# Frankie_KIT.net
KiCad netlist of a schematic drawn in EAGLE
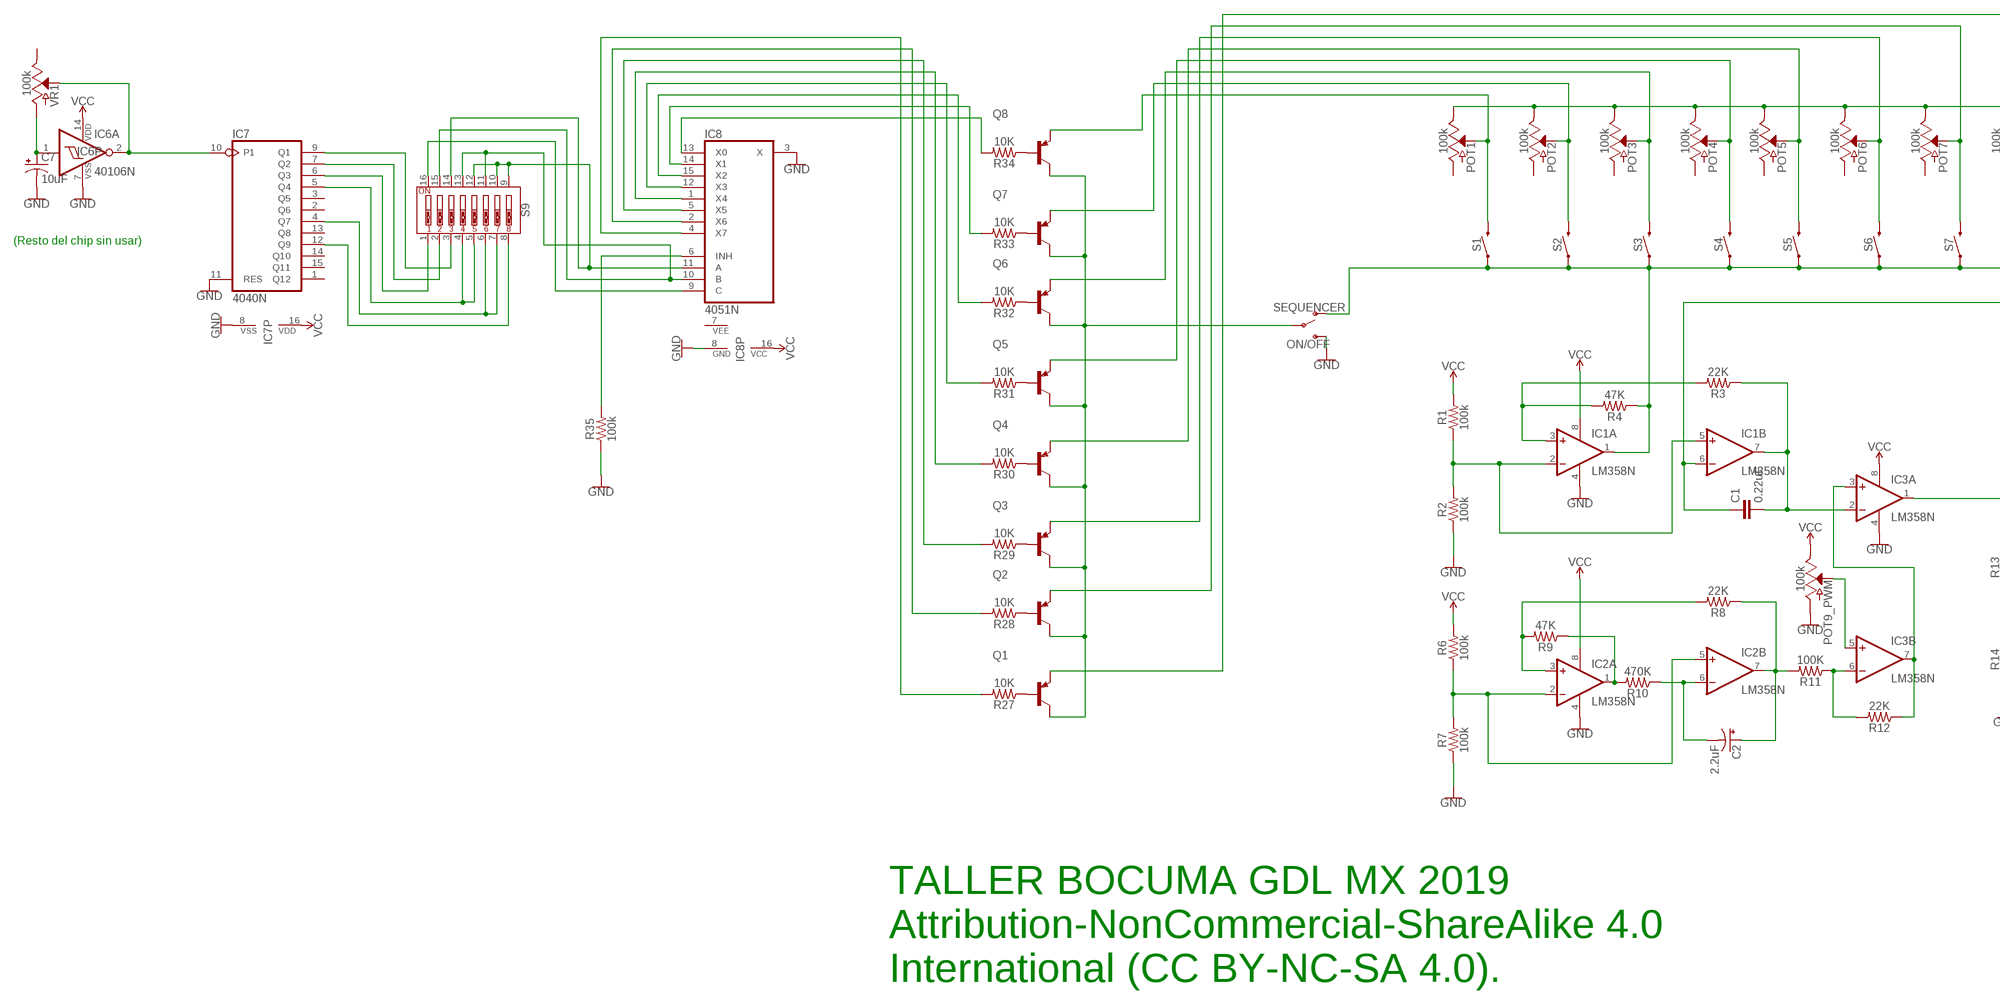
[diagram p0: schematic, sheet 1, part 1 of 2]
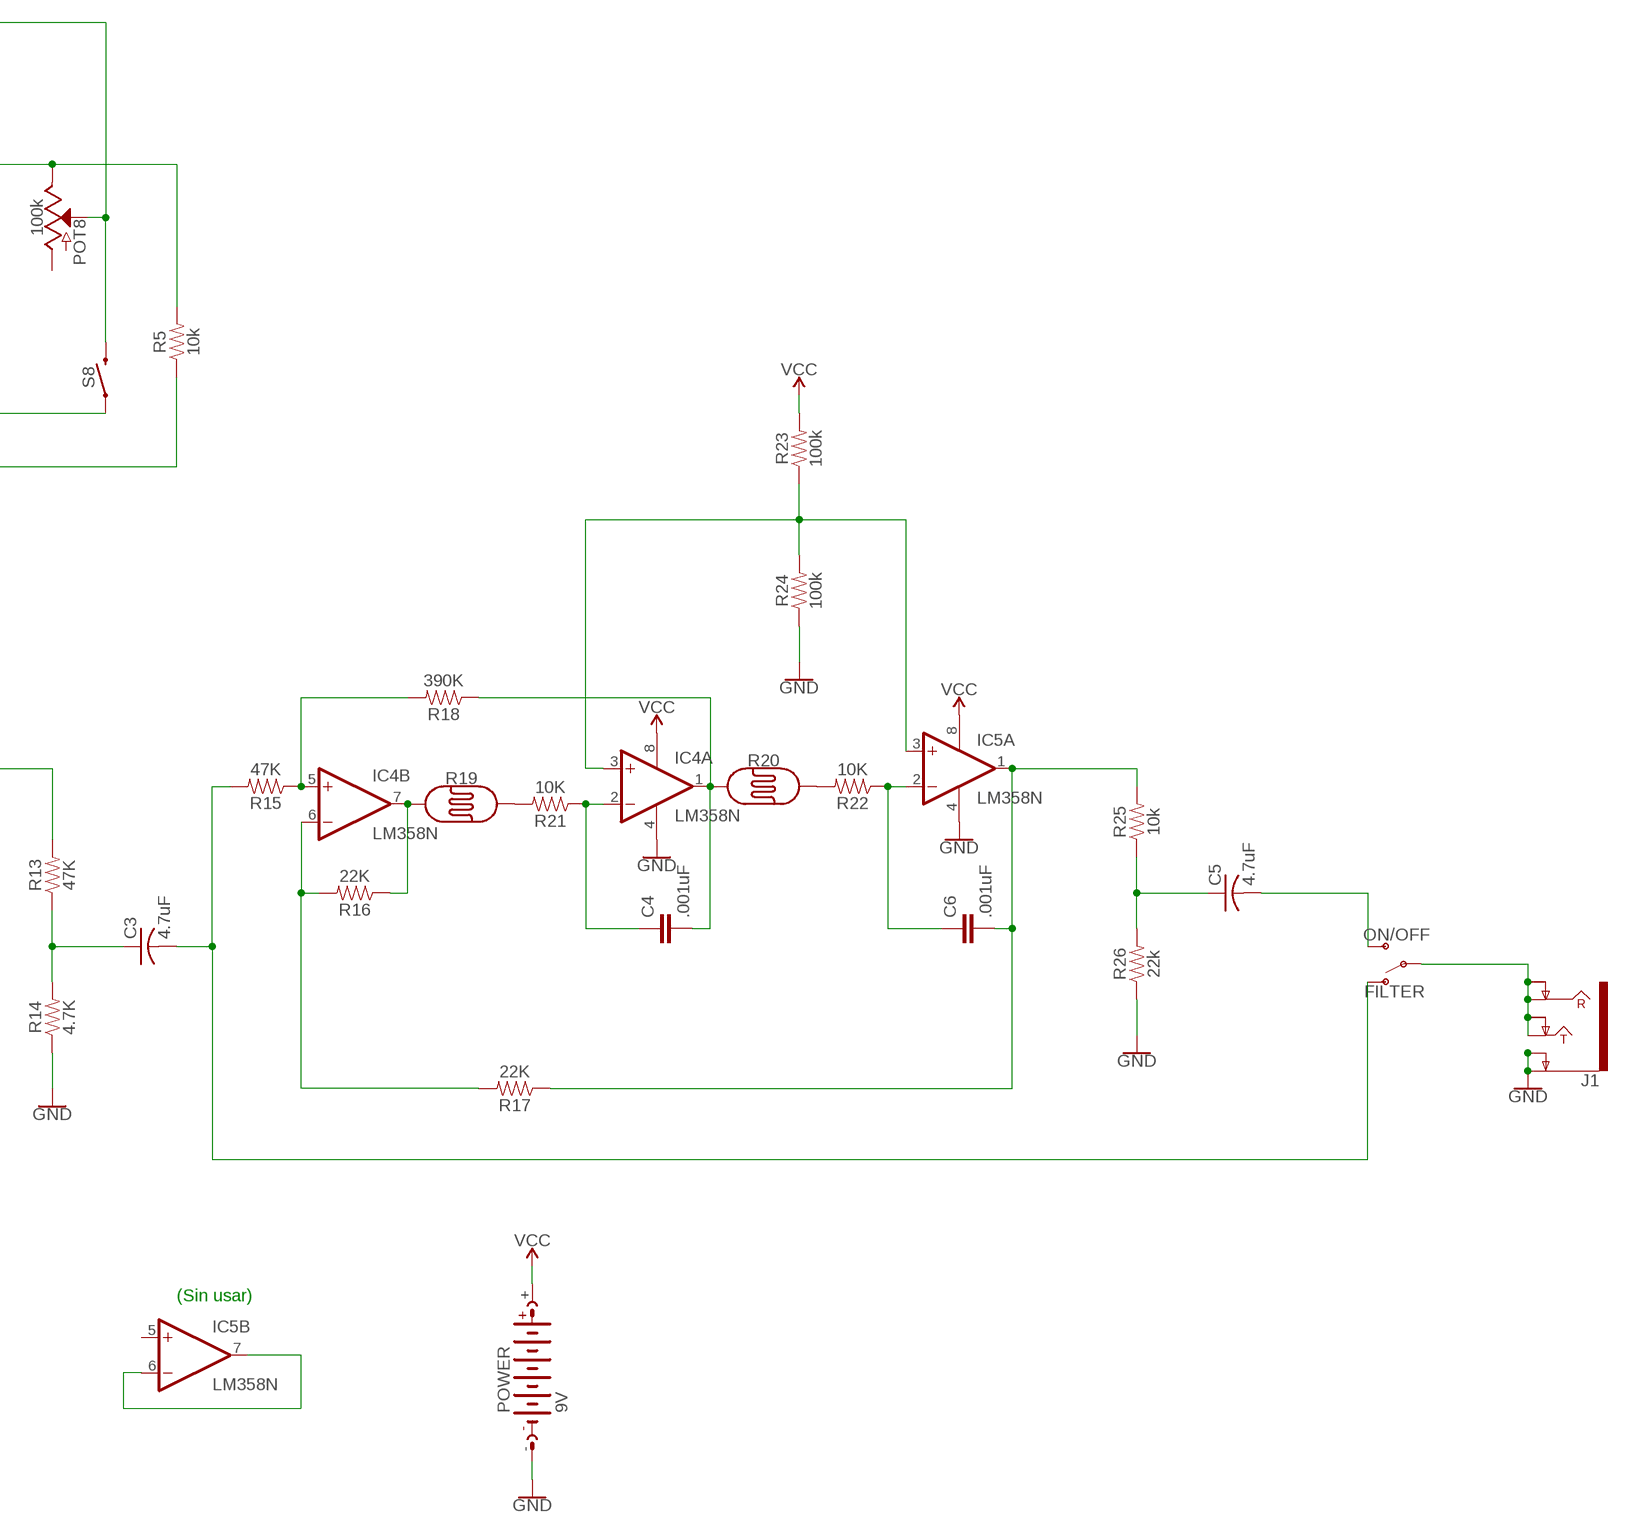
[diagram p1: schematic, sheet 1, part 2 of 2]

(export (version "E")
  (design (tool "Eeschema 10.0.6"))
  (components
    (comp (ref "C1")
      (value "0.22uF")
      (footprint "eagle-import:C5B2.5")
      (libsource (lib "eagle-import") (part "C5/2.5"))
    )
    (comp (ref "C2")
      (value "2.2uF")
      (footprint "eagle-import:CPOL-RADIAL-2.5MM-5MM-KIT")
      (libsource (lib "eagle-import") (part "10UF-POLAR-RADIAL-2.5MM-KIT-25V-20%"))
    )
    (comp (ref "C3")
      (value "4.7uF")
      (footprint "eagle-import:C050-025X075")
      (libsource (lib "eagle-import") (part "C-US050-025X075"))
    )
    (comp (ref "C4")
      (value ".001uF")
      (footprint "eagle-import:C5B2.5")
      (libsource (lib "eagle-import") (part "C5/2.5"))
    )
    (comp (ref "C5")
      (value "4.7uF")
      (footprint "eagle-import:C050-025X075")
      (libsource (lib "eagle-import") (part "C-US050-025X075"))
    )
    (comp (ref "C6")
      (value ".001uF")
      (footprint "eagle-import:C5B2.5")
      (libsource (lib "eagle-import") (part "C5/2.5"))
    )
    (comp (ref "C7")
      (value "10uF")
      (footprint "eagle-import:CPOL-RADIAL-2.5MM-5MM-KIT")
      (libsource (lib "eagle-import") (part "10UF-POLAR-RADIAL-2.5MM-KIT-25V-20%"))
    )
    (comp (ref "FILTER")
      (value "ON/OFF")
      (footprint "eagle-import:SWITCH_SPDT_PTH_11.6X4.0MM_KIT")
      (libsource (lib "eagle-import") (part "SWITCH-SPDT-PTH-11.6X4.0MM-KIT"))
    )
    (comp (ref "IC1")
      (value "LM358N")
      (footprint "eagle-import:DIL08")
      (libsource (lib "eagle-import") (part "LM358N"))
    )
    (comp (ref "IC2")
      (value "LM358N")
      (footprint "eagle-import:DIL08")
      (libsource (lib "eagle-import") (part "LM358N"))
    )
    (comp (ref "IC3")
      (value "LM358N")
      (footprint "eagle-import:DIL08")
      (libsource (lib "eagle-import") (part "LM358N"))
    )
    (comp (ref "IC4")
      (value "LM358N")
      (footprint "eagle-import:DIL08")
      (libsource (lib "eagle-import") (part "LM358N"))
    )
    (comp (ref "IC5")
      (value "LM358N")
      (footprint "eagle-import:DIL08")
      (libsource (lib "eagle-import") (part "LM358N"))
    )
    (comp (ref "IC6")
      (value "40106N")
      (footprint "eagle-import:DIL14")
      (libsource (lib "eagle-import") (part "40106N"))
    )
    (comp (ref "IC7")
      (value "4040N")
      (footprint "eagle-import:DIL16")
      (libsource (lib "eagle-import") (part "4040N"))
    )
    (comp (ref "IC8")
      (value "4051N")
      (footprint "eagle-import:DIL16")
      (libsource (lib "eagle-import") (part "4051N"))
    )
    (comp (ref "J1")
      (value "AUDIO_JACK_TRS_0.25\"_PTH_RA")
      (footprint "eagle-import:AUDIO_JACK_0.25__TRS_PTH_RA")
      (libsource (lib "eagle-import") (part "AUDIO_JACK_TRS_0.25{dblquote}_PTH_RA"))
    )
    (comp (ref "POT1")
      (value "100k")
      (footprint "eagle-import:POT-PTH-ALPS-KIT")
      (libsource (lib "eagle-import") (part "POTENTIOMETER-PTH-9MM-1/20W-20%-KIT"))
    )
    (comp (ref "POT2")
      (value "100k")
      (footprint "eagle-import:POT-PTH-ALPS-KIT")
      (libsource (lib "eagle-import") (part "POTENTIOMETER-PTH-9MM-1/20W-20%-KIT"))
    )
    (comp (ref "POT3")
      (value "100k")
      (footprint "eagle-import:POT-PTH-ALPS-KIT")
      (libsource (lib "eagle-import") (part "POTENTIOMETER-PTH-9MM-1/20W-20%-KIT"))
    )
    (comp (ref "POT4")
      (value "100k")
      (footprint "eagle-import:POT-PTH-ALPS-KIT")
      (libsource (lib "eagle-import") (part "POTENTIOMETER-PTH-9MM-1/20W-20%-KIT"))
    )
    (comp (ref "POT5")
      (value "100k")
      (footprint "eagle-import:POT-PTH-ALPS-KIT")
      (libsource (lib "eagle-import") (part "POTENTIOMETER-PTH-9MM-1/20W-20%-KIT"))
    )
    (comp (ref "POT6")
      (value "100k")
      (footprint "eagle-import:POT-PTH-ALPS-KIT")
      (libsource (lib "eagle-import") (part "POTENTIOMETER-PTH-9MM-1/20W-20%-KIT"))
    )
    (comp (ref "POT7")
      (value "100k")
      (footprint "eagle-import:POT-PTH-ALPS-KIT")
      (libsource (lib "eagle-import") (part "POTENTIOMETER-PTH-9MM-1/20W-20%-KIT"))
    )
    (comp (ref "POT8")
      (value "100k")
      (footprint "eagle-import:POT-PTH-ALPS-KIT")
      (libsource (lib "eagle-import") (part "POTENTIOMETER-PTH-9MM-1/20W-20%-KIT"))
    )
    (comp (ref "POT9_PWM")
      (value "100k")
      (footprint "eagle-import:POT-PTH-ALPS-KIT")
      (libsource (lib "eagle-import") (part "POTENTIOMETER-PTH-9MM-1/20W-20%-KIT"))
    )
    (comp (ref "POWER")
      (value "9V")
      (footprint "eagle-import:AB9V")
      (libsource (lib "eagle-import") (part "AB9V"))
    )
    (comp (ref "Q1")
      (value "2N3906")
      (footprint "eagle-import:TO92")
      (libsource (lib "eagle-import") (part "2N3906"))
    )
    (comp (ref "Q2")
      (value "2N3906")
      (footprint "eagle-import:TO92")
      (libsource (lib "eagle-import") (part "2N3906"))
    )
    (comp (ref "Q3")
      (value "2N3906")
      (footprint "eagle-import:TO92")
      (libsource (lib "eagle-import") (part "2N3906"))
    )
    (comp (ref "Q4")
      (value "2N3906")
      (footprint "eagle-import:TO92")
      (libsource (lib "eagle-import") (part "2N3906"))
    )
    (comp (ref "Q5")
      (value "2N3906")
      (footprint "eagle-import:TO92")
      (libsource (lib "eagle-import") (part "2N3906"))
    )
    (comp (ref "Q6")
      (value "2N3906")
      (footprint "eagle-import:TO92")
      (libsource (lib "eagle-import") (part "2N3906"))
    )
    (comp (ref "Q7")
      (value "2N3906")
      (footprint "eagle-import:TO92")
      (libsource (lib "eagle-import") (part "2N3906"))
    )
    (comp (ref "Q8")
      (value "2N3906")
      (footprint "eagle-import:TO92")
      (libsource (lib "eagle-import") (part "2N3906"))
    )
    (comp (ref "R1")
      (value "100k")
      (footprint "eagle-import:AXIAL-0.3")
      (libsource (lib "eagle-import") (part "100KOHM-HORIZ-1/4W-5%"))
    )
    (comp (ref "R2")
      (value "100k")
      (footprint "eagle-import:AXIAL-0.3")
      (libsource (lib "eagle-import") (part "100KOHM-HORIZ-1/4W-5%"))
    )
    (comp (ref "R3")
      (value "22K")
      (footprint "eagle-import:AXIAL-0.3")
      (libsource (lib "eagle-import") (part "100KOHM-HORIZ-1/4W-5%"))
    )
    (comp (ref "R4")
      (value "47K")
      (footprint "eagle-import:AXIAL-0.3")
      (libsource (lib "eagle-import") (part "100KOHM-HORIZ-1/4W-5%"))
    )
    (comp (ref "R5")
      (value "10k")
      (footprint "eagle-import:AXIAL-0.3")
      (libsource (lib "eagle-import") (part "100KOHM-HORIZ-1/4W-5%"))
    )
    (comp (ref "R6")
      (value "100k")
      (footprint "eagle-import:AXIAL-0.3")
      (libsource (lib "eagle-import") (part "100KOHM-HORIZ-1/4W-5%"))
    )
    (comp (ref "R7")
      (value "100k")
      (footprint "eagle-import:AXIAL-0.3")
      (libsource (lib "eagle-import") (part "100KOHM-HORIZ-1/4W-5%"))
    )
    (comp (ref "R8")
      (value "22K")
      (footprint "eagle-import:AXIAL-0.3")
      (libsource (lib "eagle-import") (part "100KOHM-HORIZ-1/4W-5%"))
    )
    (comp (ref "R9")
      (value "47K")
      (footprint "eagle-import:AXIAL-0.3")
      (libsource (lib "eagle-import") (part "100KOHM-HORIZ-1/4W-5%"))
    )
    (comp (ref "R10")
      (value "470K")
      (footprint "eagle-import:AXIAL-0.3")
      (libsource (lib "eagle-import") (part "100KOHM-HORIZ-1/4W-5%"))
    )
    (comp (ref "R11")
      (value "100K")
      (footprint "eagle-import:AXIAL-0.3")
      (libsource (lib "eagle-import") (part "100KOHM-HORIZ-1/4W-5%"))
    )
    (comp (ref "R12")
      (value "22K")
      (footprint "eagle-import:AXIAL-0.3")
      (libsource (lib "eagle-import") (part "100KOHM-HORIZ-1/4W-5%"))
    )
    (comp (ref "R13")
      (value "47K")
      (footprint "eagle-import:AXIAL-0.3")
      (libsource (lib "eagle-import") (part "100KOHM-HORIZ-1/4W-5%"))
    )
    (comp (ref "R14")
      (value "4.7K")
      (footprint "eagle-import:AXIAL-0.3")
      (libsource (lib "eagle-import") (part "100KOHM-HORIZ-1/4W-5%"))
    )
    (comp (ref "R15")
      (value "47K")
      (footprint "eagle-import:AXIAL-0.3")
      (libsource (lib "eagle-import") (part "100KOHM-HORIZ-1/4W-5%"))
    )
    (comp (ref "R16")
      (value "22K")
      (footprint "eagle-import:AXIAL-0.3")
      (libsource (lib "eagle-import") (part "100KOHM-HORIZ-1/4W-5%"))
    )
    (comp (ref "R17")
      (value "22K")
      (footprint "eagle-import:AXIAL-0.3")
      (libsource (lib "eagle-import") (part "100KOHM-HORIZ-1/4W-5%"))
    )
    (comp (ref "R18")
      (value "390K")
      (footprint "eagle-import:AXIAL-0.3")
      (libsource (lib "eagle-import") (part "100KOHM-HORIZ-1/4W-5%"))
    )
    (comp (ref "R19")
      (value "PHOTOCELLPTH-KIT")
      (footprint "eagle-import:PHOTOCELL-KIT")
      (libsource (lib "eagle-import") (part "PHOTOCELLPTH-KIT"))
    )
    (comp (ref "R20")
      (value "PHOTOCELLPTH-KIT")
      (footprint "eagle-import:PHOTOCELL-KIT")
      (libsource (lib "eagle-import") (part "PHOTOCELLPTH-KIT"))
    )
    (comp (ref "R21")
      (value "10K")
      (footprint "eagle-import:AXIAL-0.3")
      (libsource (lib "eagle-import") (part "100KOHM-HORIZ-1/4W-5%"))
    )
    (comp (ref "R22")
      (value "10K")
      (footprint "eagle-import:AXIAL-0.3")
      (libsource (lib "eagle-import") (part "100KOHM-HORIZ-1/4W-5%"))
    )
    (comp (ref "R23")
      (value "100k")
      (footprint "eagle-import:AXIAL-0.3")
      (libsource (lib "eagle-import") (part "100KOHM-HORIZ-1/4W-5%"))
    )
    (comp (ref "R24")
      (value "100k")
      (footprint "eagle-import:AXIAL-0.3")
      (libsource (lib "eagle-import") (part "100KOHM-HORIZ-1/4W-5%"))
    )
    (comp (ref "R25")
      (value "10k")
      (footprint "eagle-import:AXIAL-0.3")
      (libsource (lib "eagle-import") (part "100KOHM-HORIZ-1/4W-5%"))
    )
    (comp (ref "R26")
      (value "22k")
      (footprint "eagle-import:AXIAL-0.3")
      (libsource (lib "eagle-import") (part "100KOHM-HORIZ-1/4W-5%"))
    )
    (comp (ref "R27")
      (value "10K")
      (footprint "eagle-import:AXIAL-0.3")
      (libsource (lib "eagle-import") (part "100KOHM-HORIZ-1/4W-5%"))
    )
    (comp (ref "R28")
      (value "10K")
      (footprint "eagle-import:AXIAL-0.3")
      (libsource (lib "eagle-import") (part "100KOHM-HORIZ-1/4W-5%"))
    )
    (comp (ref "R29")
      (value "10K")
      (footprint "eagle-import:AXIAL-0.3")
      (libsource (lib "eagle-import") (part "100KOHM-HORIZ-1/4W-5%"))
    )
    (comp (ref "R30")
      (value "10K")
      (footprint "eagle-import:AXIAL-0.3")
      (libsource (lib "eagle-import") (part "100KOHM-HORIZ-1/4W-5%"))
    )
    (comp (ref "R31")
      (value "10K")
      (footprint "eagle-import:AXIAL-0.3")
      (libsource (lib "eagle-import") (part "100KOHM-HORIZ-1/4W-5%"))
    )
    (comp (ref "R32")
      (value "10K")
      (footprint "eagle-import:AXIAL-0.3")
      (libsource (lib "eagle-import") (part "100KOHM-HORIZ-1/4W-5%"))
    )
    (comp (ref "R33")
      (value "10K")
      (footprint "eagle-import:AXIAL-0.3")
      (libsource (lib "eagle-import") (part "100KOHM-HORIZ-1/4W-5%"))
    )
    (comp (ref "R34")
      (value "10K")
      (footprint "eagle-import:AXIAL-0.3")
      (libsource (lib "eagle-import") (part "100KOHM-HORIZ-1/4W-5%"))
    )
    (comp (ref "R35")
      (value "100k")
      (footprint "eagle-import:AXIAL-0.3")
      (libsource (lib "eagle-import") (part "100KOHM-HORIZ-1/4W-5%"))
    )
    (comp (ref "S1")
      (value "MOMENTARY-SWITCH-SPST-PTH-12MM")
      (footprint "eagle-import:TACTILE_SWITCH_PTH_12MM")
      (libsource (lib "eagle-import") (part "MOMENTARY-SWITCH-SPST-PTH-12MM"))
    )
    (comp (ref "S2")
      (value "MOMENTARY-SWITCH-SPST-PTH-12MM")
      (footprint "eagle-import:TACTILE_SWITCH_PTH_12MM")
      (libsource (lib "eagle-import") (part "MOMENTARY-SWITCH-SPST-PTH-12MM"))
    )
    (comp (ref "S3")
      (value "MOMENTARY-SWITCH-SPST-PTH-12MM")
      (footprint "eagle-import:TACTILE_SWITCH_PTH_12MM")
      (libsource (lib "eagle-import") (part "MOMENTARY-SWITCH-SPST-PTH-12MM"))
    )
    (comp (ref "S4")
      (value "MOMENTARY-SWITCH-SPST-PTH-12MM")
      (footprint "eagle-import:TACTILE_SWITCH_PTH_12MM")
      (libsource (lib "eagle-import") (part "MOMENTARY-SWITCH-SPST-PTH-12MM"))
    )
    (comp (ref "S5")
      (value "MOMENTARY-SWITCH-SPST-PTH-12MM")
      (footprint "eagle-import:TACTILE_SWITCH_PTH_12MM")
      (libsource (lib "eagle-import") (part "MOMENTARY-SWITCH-SPST-PTH-12MM"))
    )
    (comp (ref "S6")
      (value "MOMENTARY-SWITCH-SPST-PTH-12MM")
      (footprint "eagle-import:TACTILE_SWITCH_PTH_12MM")
      (libsource (lib "eagle-import") (part "MOMENTARY-SWITCH-SPST-PTH-12MM"))
    )
    (comp (ref "S7")
      (value "MOMENTARY-SWITCH-SPST-PTH-12MM")
      (footprint "eagle-import:TACTILE_SWITCH_PTH_12MM")
      (libsource (lib "eagle-import") (part "MOMENTARY-SWITCH-SPST-PTH-12MM"))
    )
    (comp (ref "S8")
      (value "MOMENTARY-SWITCH-SPST-PTH-12MM")
      (footprint "eagle-import:TACTILE_SWITCH_PTH_12MM")
      (libsource (lib "eagle-import") (part "MOMENTARY-SWITCH-SPST-PTH-12MM"))
    )
    (comp (ref "S9")
      (value "DIP-08-PTH")
      (footprint "eagle-import:DIPSWITCH-08")
      (libsource (lib "eagle-import") (part "DIP-08-PTH"))
    )
    (comp (ref "SEQUENCER")
      (value "ON/OFF")
      (footprint "eagle-import:SWITCH_SPDT_PTH_11.6X4.0MM_KIT")
      (libsource (lib "eagle-import") (part "SWITCH-SPDT-PTH-11.6X4.0MM-KIT"))
    )
    (comp (ref "VR1")
      (value "100k")
      (footprint "eagle-import:POT-PTH-ALPS-KIT")
      (libsource (lib "eagle-import") (part "POTENTIOMETER-PTH-9MM-1/20W-20%-KIT"))
    )
  )
  (nets
    (net (code "1") (name "/VEE") (class "Default")
      (node (ref "IC8") (pin "7") (pinfunction "VEE_7") (pintype "power_in"))
    )
    (net (code "2") (name "GND") (class "Default")
      (node (ref "C7") (pin "2") (pinfunction "-_2") (pintype "passive"))
      (node (ref "IC1") (pin "4") (pinfunction "V-_4") (pintype "power_in"))
      (node (ref "IC2") (pin "4") (pinfunction "V-_4") (pintype "power_in"))
      (node (ref "IC3") (pin "4") (pinfunction "V-_4") (pintype "power_in"))
      (node (ref "IC4") (pin "4") (pinfunction "V-_4") (pintype "power_in"))
      (node (ref "IC5") (pin "4") (pinfunction "V-_4") (pintype "power_in"))
      (node (ref "IC6") (pin "7") (pinfunction "VSS_7") (pintype "power_in"))
      (node (ref "IC7") (pin "11") (pinfunction "RES_11") (pintype "input"))
      (node (ref "IC7") (pin "8") (pinfunction "VSS_8") (pintype "power_in"))
      (node (ref "IC8") (pin "3") (pinfunction "X_3") (pintype "bidirectional"))
      (node (ref "IC8") (pin "8") (pinfunction "GND_8") (pintype "power_in"))
      (node (ref "J1") (pin "SLEEVE") (pinfunction "EARTH_SLEEVE") (pintype "bidirectional"))
      (node (ref "J1") (pin "SLEEVE-NORM") (pinfunction "EARTH-NORM_SLEEVE-NORM") (pintype "bidirectional"))
      (node (ref "POT9_PWM") (pin "P$3") (pinfunction "A_P$3") (pintype "passive"))
      (node (ref "POWER") (pin "-") (pinfunction "-_-") (pintype "passive"))
      (node (ref "R14") (pin "P$1") (pinfunction "1_P$1") (pintype "passive"))
      (node (ref "R2") (pin "P$1") (pinfunction "1_P$1") (pintype "passive"))
      (node (ref "R24") (pin "P$1") (pinfunction "1_P$1") (pintype "passive"))
      (node (ref "R26") (pin "P$1") (pinfunction "1_P$1") (pintype "passive"))
      (node (ref "R35") (pin "P$1") (pinfunction "1_P$1") (pintype "passive"))
      (node (ref "R7") (pin "P$1") (pinfunction "1_P$1") (pintype "passive"))
      (node (ref "SEQUENCER") (pin "3") (pinfunction "S_3") (pintype "passive"))
    )
    (net (code "3") (name "Net-(C2-+)") (class "Default")
      (node (ref "C2") (pin "1") (pinfunction "+_1") (pintype "passive"))
      (node (ref "IC2") (pin "7") (pinfunction "OUT_7") (pintype "output"))
      (node (ref "R11") (pin "P$2") (pinfunction "2_P$2") (pintype "passive"))
      (node (ref "R8") (pin "P$1") (pinfunction "1_P$1") (pintype "passive"))
    )
    (net (code "4") (name "Net-(C2--)") (class "Default")
      (node (ref "C2") (pin "2") (pinfunction "-_2") (pintype "passive"))
      (node (ref "IC2") (pin "6") (pinfunction "-IN_6") (pintype "input"))
      (node (ref "R10") (pin "P$1") (pinfunction "1_P$1") (pintype "passive"))
    )
    (net (code "5") (name "Net-(C7-+)") (class "Default")
      (node (ref "C7") (pin "1") (pinfunction "+_1") (pintype "passive"))
      (node (ref "IC6") (pin "1") (pinfunction "I_1") (pintype "input"))
      (node (ref "VR1") (pin "P$3") (pinfunction "A_P$3") (pintype "passive"))
    )
    (net (code "6") (name "Net-(FILTER-O)") (class "Default")
      (node (ref "C3") (pin "2") (pinfunction "2_2") (pintype "passive"))
      (node (ref "FILTER") (pin "1") (pinfunction "O_1") (pintype "passive"))
      (node (ref "R15") (pin "P$2") (pinfunction "2_P$2") (pintype "passive"))
    )
    (net (code "7") (name "Net-(FILTER-P)") (class "Default")
      (node (ref "FILTER") (pin "2") (pinfunction "P_2") (pintype "passive"))
      (node (ref "J1") (pin "RING") (pinfunction "RING_RING") (pintype "bidirectional"))
      (node (ref "J1") (pin "RING-NORM") (pinfunction "RING-NORM_RING-NORM") (pintype "bidirectional"))
      (node (ref "J1") (pin "TIP") (pinfunction "TIP_TIP") (pintype "bidirectional"))
      (node (ref "J1") (pin "TIP-NORM") (pinfunction "TIP-NORM_TIP-NORM") (pintype "bidirectional"))
    )
    (net (code "8") (name "Net-(FILTER-S)") (class "Default")
      (node (ref "C5") (pin "2") (pinfunction "2_2") (pintype "passive"))
      (node (ref "FILTER") (pin "3") (pinfunction "S_3") (pintype "passive"))
    )
    (net (code "9") (name "Net-(IC1A-+IN)") (class "Default")
      (node (ref "IC1") (pin "3") (pinfunction "+IN_3") (pintype "input"))
      (node (ref "R3") (pin "P$2") (pinfunction "2_P$2") (pintype "passive"))
      (node (ref "R4") (pin "P$2") (pinfunction "2_P$2") (pintype "passive"))
    )
    (net (code "10") (name "Net-(IC1A--IN)") (class "Default")
      (node (ref "IC1") (pin "2") (pinfunction "-IN_2") (pintype "input"))
      (node (ref "IC1") (pin "5") (pinfunction "+IN_5") (pintype "input"))
      (node (ref "R1") (pin "P$1") (pinfunction "1_P$1") (pintype "passive"))
      (node (ref "R2") (pin "P$2") (pinfunction "2_P$2") (pintype "passive"))
    )
    (net (code "11") (name "Net-(IC1A-OUT)") (class "Default")
      (node (ref "IC1") (pin "1") (pinfunction "OUT_1") (pintype "output"))
      (node (ref "R4") (pin "P$1") (pinfunction "1_P$1") (pintype "passive"))
      (node (ref "S1") (pin "1") (pinfunction "1_1") (pintype "passive"))
      (node (ref "S2") (pin "1") (pinfunction "1_1") (pintype "passive"))
      (node (ref "S3") (pin "1") (pinfunction "1_1") (pintype "passive"))
      (node (ref "S4") (pin "1") (pinfunction "1_1") (pintype "passive"))
      (node (ref "S5") (pin "1") (pinfunction "1_1") (pintype "passive"))
      (node (ref "S6") (pin "1") (pinfunction "1_1") (pintype "passive"))
      (node (ref "S7") (pin "1") (pinfunction "1_1") (pintype "passive"))
      (node (ref "S8") (pin "1") (pinfunction "1_1") (pintype "passive"))
      (node (ref "SEQUENCER") (pin "1") (pinfunction "O_1") (pintype "passive"))
    )
    (net (code "12") (name "Net-(IC1B--IN)") (class "Default")
      (node (ref "C1") (pin "1") (pinfunction "1_1") (pintype "passive"))
      (node (ref "IC1") (pin "6") (pinfunction "-IN_6") (pintype "input"))
      (node (ref "R5") (pin "P$1") (pinfunction "1_P$1") (pintype "passive"))
    )
    (net (code "13") (name "Net-(IC1B-OUT)") (class "Default")
      (node (ref "C1") (pin "2") (pinfunction "2_2") (pintype "passive"))
      (node (ref "IC1") (pin "7") (pinfunction "OUT_7") (pintype "output"))
      (node (ref "IC3") (pin "2") (pinfunction "-IN_2") (pintype "input"))
      (node (ref "R3") (pin "P$1") (pinfunction "1_P$1") (pintype "passive"))
    )
    (net (code "14") (name "Net-(IC2A-+IN)") (class "Default")
      (node (ref "IC2") (pin "3") (pinfunction "+IN_3") (pintype "input"))
      (node (ref "R8") (pin "P$2") (pinfunction "2_P$2") (pintype "passive"))
      (node (ref "R9") (pin "P$2") (pinfunction "2_P$2") (pintype "passive"))
    )
    (net (code "15") (name "Net-(IC2A--IN)") (class "Default")
      (node (ref "IC2") (pin "2") (pinfunction "-IN_2") (pintype "input"))
      (node (ref "IC2") (pin "5") (pinfunction "+IN_5") (pintype "input"))
      (node (ref "R6") (pin "P$1") (pinfunction "1_P$1") (pintype "passive"))
      (node (ref "R7") (pin "P$2") (pinfunction "2_P$2") (pintype "passive"))
    )
    (net (code "16") (name "Net-(IC2A-OUT)") (class "Default")
      (node (ref "IC2") (pin "1") (pinfunction "OUT_1") (pintype "output"))
      (node (ref "R10") (pin "P$2") (pinfunction "2_P$2") (pintype "passive"))
      (node (ref "R9") (pin "P$1") (pinfunction "1_P$1") (pintype "passive"))
    )
    (net (code "17") (name "Net-(IC3A-+IN)") (class "Default")
      (node (ref "IC3") (pin "3") (pinfunction "+IN_3") (pintype "input"))
      (node (ref "IC3") (pin "7") (pinfunction "OUT_7") (pintype "output"))
      (node (ref "R12") (pin "P$1") (pinfunction "1_P$1") (pintype "passive"))
    )
    (net (code "18") (name "Net-(IC3A-OUT)") (class "Default")
      (node (ref "IC3") (pin "1") (pinfunction "OUT_1") (pintype "output"))
      (node (ref "R13") (pin "P$2") (pinfunction "2_P$2") (pintype "passive"))
    )
    (net (code "19") (name "Net-(IC3B-+IN)") (class "Default")
      (node (ref "IC3") (pin "5") (pinfunction "+IN_5") (pintype "input"))
      (node (ref "POT9_PWM") (pin "P$2") (pinfunction "S_P$2") (pintype "passive"))
    )
    (net (code "20") (name "Net-(IC3B--IN)") (class "Default")
      (node (ref "IC3") (pin "6") (pinfunction "-IN_6") (pintype "input"))
      (node (ref "R11") (pin "P$1") (pinfunction "1_P$1") (pintype "passive"))
      (node (ref "R12") (pin "P$2") (pinfunction "2_P$2") (pintype "passive"))
    )
    (net (code "21") (name "Net-(IC4A-+IN)") (class "Default")
      (node (ref "IC4") (pin "3") (pinfunction "+IN_3") (pintype "input"))
      (node (ref "IC5") (pin "3") (pinfunction "+IN_3") (pintype "input"))
      (node (ref "R23") (pin "P$1") (pinfunction "1_P$1") (pintype "passive"))
      (node (ref "R24") (pin "P$2") (pinfunction "2_P$2") (pintype "passive"))
    )
    (net (code "22") (name "Net-(IC4A--IN)") (class "Default")
      (node (ref "C4") (pin "1") (pinfunction "1_1") (pintype "passive"))
      (node (ref "IC4") (pin "2") (pinfunction "-IN_2") (pintype "input"))
      (node (ref "R21") (pin "P$1") (pinfunction "1_P$1") (pintype "passive"))
    )
    (net (code "23") (name "Net-(IC4A-OUT)") (class "Default")
      (node (ref "C4") (pin "2") (pinfunction "2_2") (pintype "passive"))
      (node (ref "IC4") (pin "1") (pinfunction "OUT_1") (pintype "output"))
      (node (ref "R18") (pin "P$1") (pinfunction "1_P$1") (pintype "passive"))
      (node (ref "R20") (pin "1") (pinfunction "P$1_1") (pintype "bidirectional"))
    )
    (net (code "24") (name "Net-(IC4B-+IN)") (class "Default")
      (node (ref "IC4") (pin "5") (pinfunction "+IN_5") (pintype "input"))
      (node (ref "R15") (pin "P$1") (pinfunction "1_P$1") (pintype "passive"))
      (node (ref "R18") (pin "P$2") (pinfunction "2_P$2") (pintype "passive"))
    )
    (net (code "25") (name "Net-(IC4B--IN)") (class "Default")
      (node (ref "IC4") (pin "6") (pinfunction "-IN_6") (pintype "input"))
      (node (ref "R16") (pin "P$2") (pinfunction "2_P$2") (pintype "passive"))
      (node (ref "R17") (pin "P$2") (pinfunction "2_P$2") (pintype "passive"))
    )
    (net (code "26") (name "Net-(IC4B-OUT)") (class "Default")
      (node (ref "IC4") (pin "7") (pinfunction "OUT_7") (pintype "output"))
      (node (ref "R16") (pin "P$1") (pinfunction "1_P$1") (pintype "passive"))
      (node (ref "R19") (pin "1") (pinfunction "P$1_1") (pintype "bidirectional"))
    )
    (net (code "27") (name "Net-(IC5A--IN)") (class "Default")
      (node (ref "C6") (pin "1") (pinfunction "1_1") (pintype "passive"))
      (node (ref "IC5") (pin "2") (pinfunction "-IN_2") (pintype "input"))
      (node (ref "R22") (pin "P$1") (pinfunction "1_P$1") (pintype "passive"))
    )
    (net (code "28") (name "Net-(IC5A-OUT)") (class "Default")
      (node (ref "C6") (pin "2") (pinfunction "2_2") (pintype "passive"))
      (node (ref "IC5") (pin "1") (pinfunction "OUT_1") (pintype "output"))
      (node (ref "R17") (pin "P$1") (pinfunction "1_P$1") (pintype "passive"))
      (node (ref "R25") (pin "P$2") (pinfunction "2_P$2") (pintype "passive"))
    )
    (net (code "29") (name "Net-(IC5B--IN)") (class "Default")
      (node (ref "IC5") (pin "6") (pinfunction "-IN_6") (pintype "input"))
      (node (ref "IC5") (pin "7") (pinfunction "OUT_7") (pintype "output"))
    )
    (net (code "30") (name "Net-(IC6A-O)") (class "Default")
      (node (ref "IC6") (pin "2") (pinfunction "O_2") (pintype "output"))
      (node (ref "IC7") (pin "10") (pinfunction "P1_10") (pintype "input"))
      (node (ref "VR1") (pin "P$2") (pinfunction "S_P$2") (pintype "passive"))
    )
    (net (code "31") (name "Net-(IC7A-Q1)") (class "Default")
      (node (ref "IC7") (pin "9") (pinfunction "Q1_9") (pintype "output"))
      (node (ref "S9") (pin "3") (pinfunction "3_3") (pintype "passive"))
    )
    (net (code "32") (name "Net-(IC7A-Q2)") (class "Default")
      (node (ref "IC7") (pin "7") (pinfunction "Q2_7") (pintype "output"))
      (node (ref "S9") (pin "2") (pinfunction "2_2") (pintype "passive"))
    )
    (net (code "33") (name "Net-(IC7A-Q3)") (class "Default")
      (node (ref "IC7") (pin "6") (pinfunction "Q3_6") (pintype "output"))
      (node (ref "S9") (pin "1") (pinfunction "1_1") (pintype "passive"))
    )
    (net (code "34") (name "Net-(IC7A-Q4)") (class "Default")
      (node (ref "IC7") (pin "5") (pinfunction "Q4_5") (pintype "output"))
      (node (ref "S9") (pin "4") (pinfunction "4_4") (pintype "passive"))
      (node (ref "S9") (pin "5") (pinfunction "5_5") (pintype "passive"))
    )
    (net (code "35") (name "Net-(IC7A-Q7)") (class "Default")
      (node (ref "IC7") (pin "4") (pinfunction "Q7_4") (pintype "output"))
      (node (ref "S9") (pin "6") (pinfunction "6_6") (pintype "passive"))
      (node (ref "S9") (pin "7") (pinfunction "7_7") (pintype "passive"))
    )
    (net (code "36") (name "Net-(IC7A-Q9)") (class "Default")
      (node (ref "IC7") (pin "12") (pinfunction "Q9_12") (pintype "output"))
      (node (ref "S9") (pin "8") (pinfunction "8_8") (pintype "passive"))
    )
    (net (code "37") (name "Net-(IC8A-A)") (class "Default")
      (node (ref "IC8") (pin "11") (pinfunction "A_11") (pintype "input"))
      (node (ref "S9") (pin "10") (pinfunction "10_10") (pintype "passive"))
      (node (ref "S9") (pin "12") (pinfunction "12_12") (pintype "passive"))
      (node (ref "S9") (pin "14") (pinfunction "14_14") (pintype "passive"))
      (node (ref "S9") (pin "9") (pinfunction "9_9") (pintype "passive"))
    )
    (net (code "38") (name "Net-(IC8A-B)") (class "Default")
      (node (ref "IC8") (pin "10") (pinfunction "B_10") (pintype "input"))
      (node (ref "S9") (pin "11") (pinfunction "11_11") (pintype "passive"))
      (node (ref "S9") (pin "13") (pinfunction "13_13") (pintype "passive"))
      (node (ref "S9") (pin "15") (pinfunction "15_15") (pintype "passive"))
    )
    (net (code "39") (name "Net-(IC8A-C)") (class "Default")
      (node (ref "IC8") (pin "9") (pinfunction "C_9") (pintype "input"))
      (node (ref "S9") (pin "16") (pinfunction "16_16") (pintype "passive"))
    )
    (net (code "40") (name "Net-(IC8A-INH)") (class "Default")
      (node (ref "IC8") (pin "6") (pinfunction "INH_6") (pintype "input"))
      (node (ref "R35") (pin "P$2") (pinfunction "2_P$2") (pintype "passive"))
    )
    (net (code "41") (name "Net-(IC8A-X0)") (class "Default")
      (node (ref "IC8") (pin "13") (pinfunction "X0_13") (pintype "bidirectional"))
      (node (ref "R34") (pin "P$2") (pinfunction "2_P$2") (pintype "passive"))
    )
    (net (code "42") (name "Net-(IC8A-X1)") (class "Default")
      (node (ref "IC8") (pin "14") (pinfunction "X1_14") (pintype "bidirectional"))
      (node (ref "R33") (pin "P$2") (pinfunction "2_P$2") (pintype "passive"))
    )
    (net (code "43") (name "Net-(IC8A-X2)") (class "Default")
      (node (ref "IC8") (pin "15") (pinfunction "X2_15") (pintype "bidirectional"))
      (node (ref "R32") (pin "P$2") (pinfunction "2_P$2") (pintype "passive"))
    )
    (net (code "44") (name "Net-(IC8A-X3)") (class "Default")
      (node (ref "IC8") (pin "12") (pinfunction "X3_12") (pintype "bidirectional"))
      (node (ref "R31") (pin "P$2") (pinfunction "2_P$2") (pintype "passive"))
    )
    (net (code "45") (name "Net-(IC8A-X4)") (class "Default")
      (node (ref "IC8") (pin "1") (pinfunction "X4_1") (pintype "bidirectional"))
      (node (ref "R30") (pin "P$2") (pinfunction "2_P$2") (pintype "passive"))
    )
    (net (code "46") (name "Net-(IC8A-X5)") (class "Default")
      (node (ref "IC8") (pin "5") (pinfunction "X5_5") (pintype "bidirectional"))
      (node (ref "R29") (pin "P$2") (pinfunction "2_P$2") (pintype "passive"))
    )
    (net (code "47") (name "Net-(IC8A-X6)") (class "Default")
      (node (ref "IC8") (pin "2") (pinfunction "X6_2") (pintype "bidirectional"))
      (node (ref "R28") (pin "P$2") (pinfunction "2_P$2") (pintype "passive"))
    )
    (net (code "48") (name "Net-(IC8A-X7)") (class "Default")
      (node (ref "IC8") (pin "4") (pinfunction "X7_4") (pintype "bidirectional"))
      (node (ref "R27") (pin "P$2") (pinfunction "2_P$2") (pintype "passive"))
    )
    (net (code "49") (name "Net-(POT1-E)") (class "Default")
      (node (ref "POT1") (pin "P$1") (pinfunction "E_P$1") (pintype "passive"))
      (node (ref "POT2") (pin "P$1") (pinfunction "E_P$1") (pintype "passive"))
      (node (ref "POT3") (pin "P$1") (pinfunction "E_P$1") (pintype "passive"))
      (node (ref "POT4") (pin "P$1") (pinfunction "E_P$1") (pintype "passive"))
      (node (ref "POT5") (pin "P$1") (pinfunction "E_P$1") (pintype "passive"))
      (node (ref "POT6") (pin "P$1") (pinfunction "E_P$1") (pintype "passive"))
      (node (ref "POT7") (pin "P$1") (pinfunction "E_P$1") (pintype "passive"))
      (node (ref "POT8") (pin "P$1") (pinfunction "E_P$1") (pintype "passive"))
      (node (ref "R5") (pin "P$2") (pinfunction "2_P$2") (pintype "passive"))
    )
    (net (code "50") (name "Net-(POT1-S)") (class "Default")
      (node (ref "POT1") (pin "P$2") (pinfunction "S_P$2") (pintype "passive"))
      (node (ref "Q8") (pin "3") (pinfunction "E_3") (pintype "passive"))
      (node (ref "S1") (pin "3") (pinfunction "2_3") (pintype "passive"))
    )
    (net (code "51") (name "Net-(POT2-S)") (class "Default")
      (node (ref "POT2") (pin "P$2") (pinfunction "S_P$2") (pintype "passive"))
      (node (ref "Q7") (pin "3") (pinfunction "E_3") (pintype "passive"))
      (node (ref "S2") (pin "3") (pinfunction "2_3") (pintype "passive"))
    )
    (net (code "52") (name "Net-(POT3-S)") (class "Default")
      (node (ref "POT3") (pin "P$2") (pinfunction "S_P$2") (pintype "passive"))
      (node (ref "Q6") (pin "3") (pinfunction "E_3") (pintype "passive"))
      (node (ref "S3") (pin "3") (pinfunction "2_3") (pintype "passive"))
    )
    (net (code "53") (name "Net-(POT4-S)") (class "Default")
      (node (ref "POT4") (pin "P$2") (pinfunction "S_P$2") (pintype "passive"))
      (node (ref "Q5") (pin "3") (pinfunction "E_3") (pintype "passive"))
      (node (ref "S4") (pin "3") (pinfunction "2_3") (pintype "passive"))
    )
    (net (code "54") (name "Net-(POT5-S)") (class "Default")
      (node (ref "POT5") (pin "P$2") (pinfunction "S_P$2") (pintype "passive"))
      (node (ref "Q4") (pin "3") (pinfunction "E_3") (pintype "passive"))
      (node (ref "S5") (pin "3") (pinfunction "2_3") (pintype "passive"))
    )
    (net (code "55") (name "Net-(POT6-S)") (class "Default")
      (node (ref "POT6") (pin "P$2") (pinfunction "S_P$2") (pintype "passive"))
      (node (ref "Q3") (pin "3") (pinfunction "E_3") (pintype "passive"))
      (node (ref "S6") (pin "3") (pinfunction "2_3") (pintype "passive"))
    )
    (net (code "56") (name "Net-(POT7-S)") (class "Default")
      (node (ref "POT7") (pin "P$2") (pinfunction "S_P$2") (pintype "passive"))
      (node (ref "Q2") (pin "3") (pinfunction "E_3") (pintype "passive"))
      (node (ref "S7") (pin "3") (pinfunction "2_3") (pintype "passive"))
    )
    (net (code "57") (name "Net-(POT8-S)") (class "Default")
      (node (ref "POT8") (pin "P$2") (pinfunction "S_P$2") (pintype "passive"))
      (node (ref "Q1") (pin "3") (pinfunction "E_3") (pintype "passive"))
      (node (ref "S8") (pin "3") (pinfunction "2_3") (pintype "passive"))
    )
    (net (code "58") (name "Net-(Q1-B)") (class "Default")
      (node (ref "Q1") (pin "2") (pinfunction "B_2") (pintype "passive"))
      (node (ref "R27") (pin "P$1") (pinfunction "1_P$1") (pintype "passive"))
    )
    (net (code "59") (name "Net-(Q1-C)") (class "Default")
      (node (ref "Q1") (pin "1") (pinfunction "C_1") (pintype "passive"))
      (node (ref "Q2") (pin "1") (pinfunction "C_1") (pintype "passive"))
      (node (ref "Q3") (pin "1") (pinfunction "C_1") (pintype "passive"))
      (node (ref "Q4") (pin "1") (pinfunction "C_1") (pintype "passive"))
      (node (ref "Q5") (pin "1") (pinfunction "C_1") (pintype "passive"))
      (node (ref "Q6") (pin "1") (pinfunction "C_1") (pintype "passive"))
      (node (ref "Q7") (pin "1") (pinfunction "C_1") (pintype "passive"))
      (node (ref "Q8") (pin "1") (pinfunction "C_1") (pintype "passive"))
      (node (ref "SEQUENCER") (pin "2") (pinfunction "P_2") (pintype "passive"))
    )
    (net (code "60") (name "Net-(Q2-B)") (class "Default")
      (node (ref "Q2") (pin "2") (pinfunction "B_2") (pintype "passive"))
      (node (ref "R28") (pin "P$1") (pinfunction "1_P$1") (pintype "passive"))
    )
    (net (code "61") (name "Net-(Q3-B)") (class "Default")
      (node (ref "Q3") (pin "2") (pinfunction "B_2") (pintype "passive"))
      (node (ref "R29") (pin "P$1") (pinfunction "1_P$1") (pintype "passive"))
    )
    (net (code "62") (name "Net-(Q4-B)") (class "Default")
      (node (ref "Q4") (pin "2") (pinfunction "B_2") (pintype "passive"))
      (node (ref "R30") (pin "P$1") (pinfunction "1_P$1") (pintype "passive"))
    )
    (net (code "63") (name "Net-(Q5-B)") (class "Default")
      (node (ref "Q5") (pin "2") (pinfunction "B_2") (pintype "passive"))
      (node (ref "R31") (pin "P$1") (pinfunction "1_P$1") (pintype "passive"))
    )
    (net (code "64") (name "Net-(Q6-B)") (class "Default")
      (node (ref "Q6") (pin "2") (pinfunction "B_2") (pintype "passive"))
      (node (ref "R32") (pin "P$1") (pinfunction "1_P$1") (pintype "passive"))
    )
    (net (code "65") (name "Net-(Q7-B)") (class "Default")
      (node (ref "Q7") (pin "2") (pinfunction "B_2") (pintype "passive"))
      (node (ref "R33") (pin "P$1") (pinfunction "1_P$1") (pintype "passive"))
    )
    (net (code "66") (name "Net-(Q8-B)") (class "Default")
      (node (ref "Q8") (pin "2") (pinfunction "B_2") (pintype "passive"))
      (node (ref "R34") (pin "P$1") (pinfunction "1_P$1") (pintype "passive"))
    )
    (net (code "67") (name "Net-(R13-1)") (class "Default")
      (node (ref "C3") (pin "1") (pinfunction "1_1") (pintype "passive"))
      (node (ref "R13") (pin "P$1") (pinfunction "1_P$1") (pintype "passive"))
      (node (ref "R14") (pin "P$2") (pinfunction "2_P$2") (pintype "passive"))
    )
    (net (code "68") (name "Net-(R19-P$2)") (class "Default")
      (node (ref "R19") (pin "2") (pinfunction "P$2_2") (pintype "bidirectional"))
      (node (ref "R21") (pin "P$2") (pinfunction "2_P$2") (pintype "passive"))
    )
    (net (code "69") (name "Net-(R20-P$2)") (class "Default")
      (node (ref "R20") (pin "2") (pinfunction "P$2_2") (pintype "bidirectional"))
      (node (ref "R22") (pin "P$2") (pinfunction "2_P$2") (pintype "passive"))
    )
    (net (code "70") (name "Net-(R25-1)") (class "Default")
      (node (ref "C5") (pin "1") (pinfunction "1_1") (pintype "passive"))
      (node (ref "R25") (pin "P$1") (pinfunction "1_P$1") (pintype "passive"))
      (node (ref "R26") (pin "P$2") (pinfunction "2_P$2") (pintype "passive"))
    )
    (net (code "71") (name "VCC") (class "Default")
      (node (ref "IC1") (pin "8") (pinfunction "V+_8") (pintype "power_in"))
      (node (ref "IC2") (pin "8") (pinfunction "V+_8") (pintype "power_in"))
      (node (ref "IC3") (pin "8") (pinfunction "V+_8") (pintype "power_in"))
      (node (ref "IC4") (pin "8") (pinfunction "V+_8") (pintype "power_in"))
      (node (ref "IC5") (pin "8") (pinfunction "V+_8") (pintype "power_in"))
      (node (ref "IC6") (pin "14") (pinfunction "VDD_14") (pintype "power_in"))
      (node (ref "IC7") (pin "16") (pinfunction "VDD_16") (pintype "power_in"))
      (node (ref "IC8") (pin "16") (pinfunction "VCC_16") (pintype "power_in"))
      (node (ref "POT9_PWM") (pin "P$1") (pinfunction "E_P$1") (pintype "passive"))
      (node (ref "POWER") (pin "+") (pinfunction "+_+") (pintype "passive"))
      (node (ref "R1") (pin "P$2") (pinfunction "2_P$2") (pintype "passive"))
      (node (ref "R23") (pin "P$2") (pinfunction "2_P$2") (pintype "passive"))
      (node (ref "R6") (pin "P$2") (pinfunction "2_P$2") (pintype "passive"))
    )
    (net (code "72") (name "unconnected-(IC5B-+IN-Pad5)") (class "Default")
      (node (ref "IC5") (pin "5") (pinfunction "+IN_5") (pintype "input"))
    )
    (net (code "73") (name "unconnected-(IC7A-Q5-Pad3)") (class "Default")
      (node (ref "IC7") (pin "3") (pinfunction "Q5_3") (pintype "output"))
    )
    (net (code "74") (name "unconnected-(IC7A-Q6-Pad2)") (class "Default")
      (node (ref "IC7") (pin "2") (pinfunction "Q6_2") (pintype "output"))
    )
    (net (code "75") (name "unconnected-(IC7A-Q8-Pad13)") (class "Default")
      (node (ref "IC7") (pin "13") (pinfunction "Q8_13") (pintype "output"))
    )
    (net (code "76") (name "unconnected-(IC7A-Q10-Pad14)") (class "Default")
      (node (ref "IC7") (pin "14") (pinfunction "Q10_14") (pintype "output"))
    )
    (net (code "77") (name "unconnected-(IC7A-Q11-Pad15)") (class "Default")
      (node (ref "IC7") (pin "15") (pinfunction "Q11_15") (pintype "output"))
    )
    (net (code "78") (name "unconnected-(IC7A-Q12-Pad1)") (class "Default")
      (node (ref "IC7") (pin "1") (pinfunction "Q12_1") (pintype "output"))
    )
    (net (code "79") (name "unconnected-(POT1-A-PadP$3)") (class "Default")
      (node (ref "POT1") (pin "P$3") (pinfunction "A_P$3") (pintype "passive"))
    )
    (net (code "80") (name "unconnected-(POT2-A-PadP$3)") (class "Default")
      (node (ref "POT2") (pin "P$3") (pinfunction "A_P$3") (pintype "passive"))
    )
    (net (code "81") (name "unconnected-(POT3-A-PadP$3)") (class "Default")
      (node (ref "POT3") (pin "P$3") (pinfunction "A_P$3") (pintype "passive"))
    )
    (net (code "82") (name "unconnected-(POT4-A-PadP$3)") (class "Default")
      (node (ref "POT4") (pin "P$3") (pinfunction "A_P$3") (pintype "passive"))
    )
    (net (code "83") (name "unconnected-(POT5-A-PadP$3)") (class "Default")
      (node (ref "POT5") (pin "P$3") (pinfunction "A_P$3") (pintype "passive"))
    )
    (net (code "84") (name "unconnected-(POT6-A-PadP$3)") (class "Default")
      (node (ref "POT6") (pin "P$3") (pinfunction "A_P$3") (pintype "passive"))
    )
    (net (code "85") (name "unconnected-(POT7-A-PadP$3)") (class "Default")
      (node (ref "POT7") (pin "P$3") (pinfunction "A_P$3") (pintype "passive"))
    )
    (net (code "86") (name "unconnected-(POT8-A-PadP$3)") (class "Default")
      (node (ref "POT8") (pin "P$3") (pinfunction "A_P$3") (pintype "passive"))
    )
    (net (code "87") (name "unconnected-(VR1-E-PadP$1)") (class "Default")
      (node (ref "VR1") (pin "P$1") (pinfunction "E_P$1") (pintype "passive"))
    )
  )
)
